# converter_schematic.net
KiCad netlist of a schematic drawn in EasyEDA
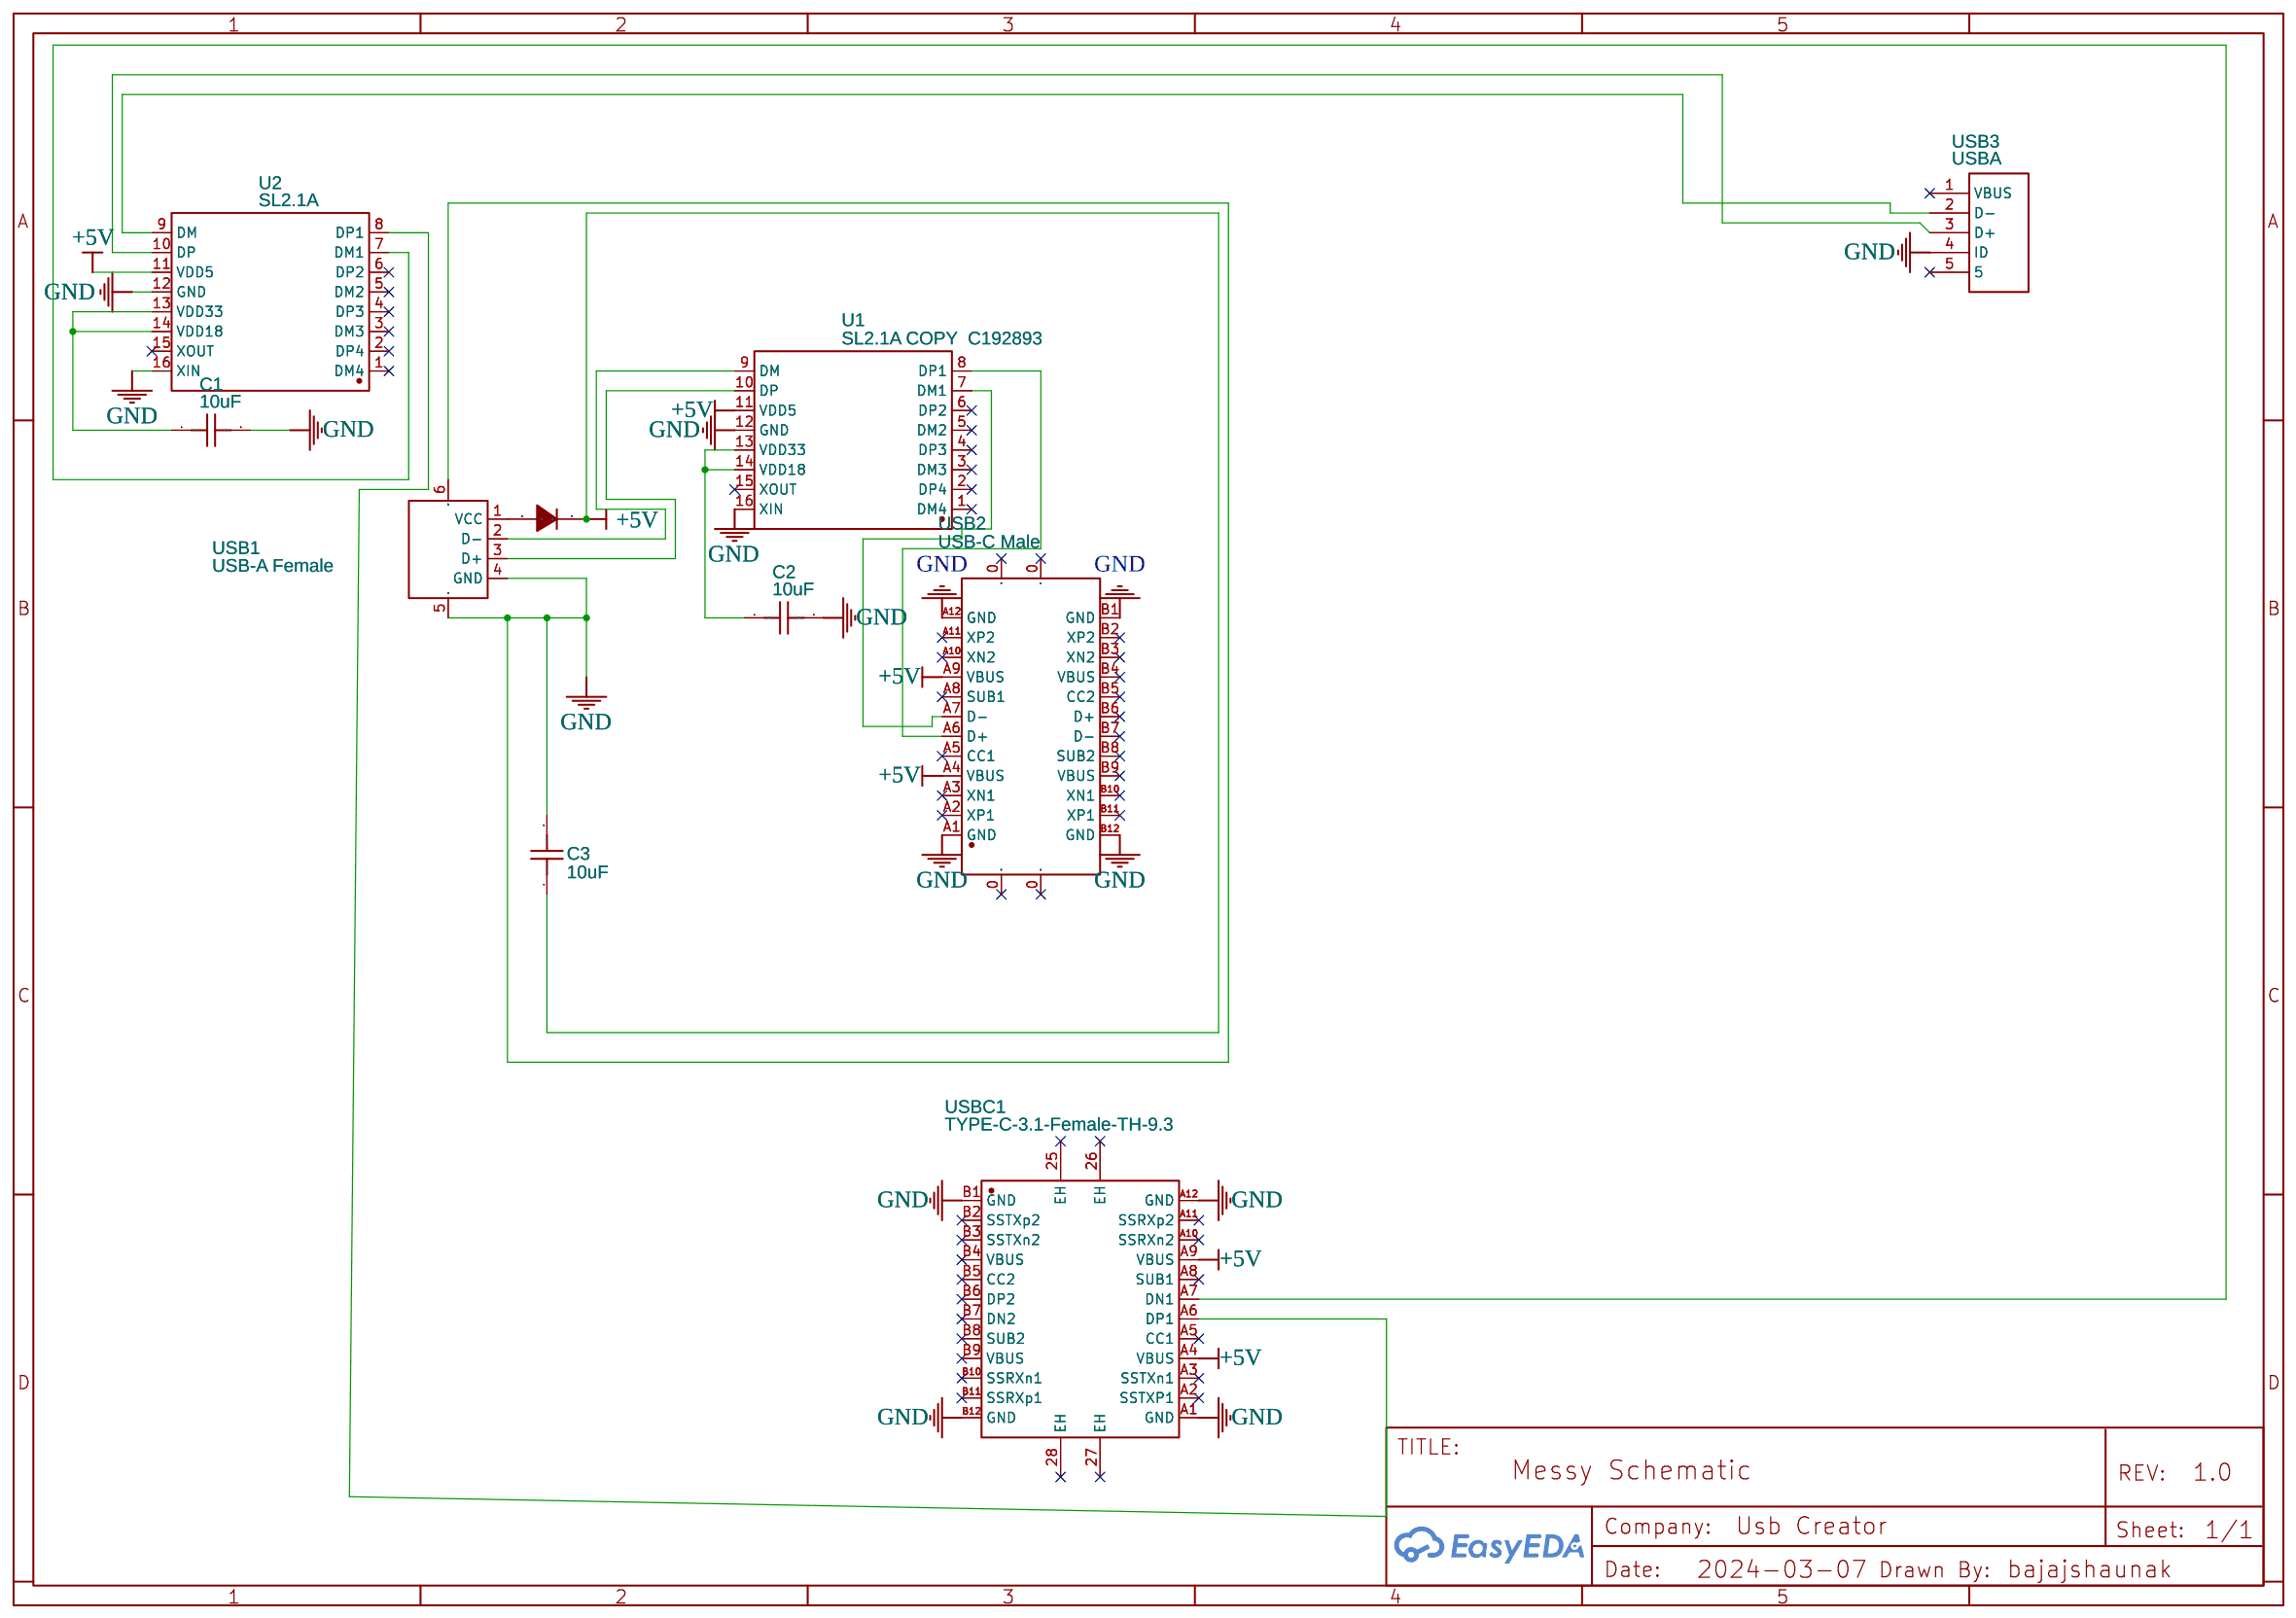
[diagram p0: schematic sheet]

(export (version "E")
  (design (tool "Eeschema 10.0.6"))
  (components
    (comp (ref "C1")
      (value "10uF")
      (fields
        (field (name "Manufacturer Part") "CL10A106KP8NNNC")
        (field (name "Manufacturer") "SAMSUNG(三星)")
      )
      (libsource (lib "") (part "CL10A106KP8NNNC"))
    )
    (comp (ref "C2")
      (value "10uF")
      (fields
        (field (name "Manufacturer Part") "CL10A106KP8NNNC")
        (field (name "Manufacturer") "SAMSUNG(三星)")
      )
      (libsource (lib "") (part "CL10A106KP8NNNC"))
    )
    (comp (ref "C3")
      (value "10uF")
      (fields
        (field (name "Manufacturer Part") "CL10A106KP8NNNC")
        (field (name "Manufacturer") "SAMSUNG(三星)")
      )
      (libsource (lib "") (part "CL10A106KP8NNNC_1"))
    )
    (comp (ref "D2")
      (value "NSR0320MW2T1G")
      (fields (field (name "Manufacturer") "onsemi(安森美)"))
      (libsource (lib "") (part "NSR0320MW2T1G"))
    )
    (comp (ref "U1")
      (value "SL2.1A COPY  C192893")
      (fields (field (name "Manufacturer Part") "SL2.1A") (field (name "Manufacturer") "CoreChips(和芯润德)"))
      (libsource (lib "") (part "SL2.1A COPY  C192893"))
    )
    (comp (ref "U2")
      (value "SL2.1A")
      (fields (field (name "Manufacturer") "CoreChips(和芯润德)"))
      (libsource (lib "") (part "SL2.1A"))
    )
    (comp (ref "USB1")
      (value "USB-A Female")
      (fields (field (name "Manufacturer Part") "USB-AF-DIP-154-HW-S") (field (name "Manufacturer") "皇捷"))
      (libsource (lib "") (part "USB-AF-DIP-154-HW-S"))
    )
    (comp (ref "USB2")
      (value "USB-C Male")
      (fields (field (name "Manufacturer Part") "USB-307HI") (field (name "Manufacturer") "HOOYA(皓宇电子)"))
      (libsource (lib "") (part "USB-307HI"))
    )
    (comp (ref "USB3")
      (value "USBA")
      (fields (field (name "Manufacturer Part") "U-USBAR04P-M001") (field (name "Manufacturer") "Ckmtw(灿科盟)"))
      (libsource (lib "") (part "U-USBAR04P-M002"))
    )
    (comp (ref "USBC1")
      (value "TYPE-C-3.1-Female-TH-9.3")
      (fields (field (name "Manufacturer Part") "918-418K2022Y40004") (field (name "Manufacturer") "精拓金"))
      (libsource (lib "") (part "TYPE-C-3.1-Female-TH-9.3"))
    )
  )
  (nets
    (net (code "1") (name "+5V") (class "Default")
      (node (ref "C3") (pin "1") (pinfunction "1_1") (pintype "unspecified"))
      (node (ref "D2") (pin "1") (pinfunction "C_1") (pintype "unspecified"))
      (node (ref "U1") (pin "11") (pinfunction "VDD5_11") (pintype "unspecified"))
      (node (ref "U2") (pin "11") (pinfunction "VDD5_11") (pintype "unspecified"))
      (node (ref "USB2") (pin "A4") (pinfunction "VBUS_A4") (pintype "unspecified"))
      (node (ref "USB2") (pin "A9") (pinfunction "VBUS_A9") (pintype "unspecified"))
      (node (ref "USBC1") (pin "A4") (pinfunction "VBUS_A4") (pintype "unspecified"))
      (node (ref "USBC1") (pin "A9") (pinfunction "VBUS_A9") (pintype "unspecified"))
    )
    (net (code "2") (name "GND") (class "Default")
      (node (ref "C1") (pin "2") (pinfunction "2_2") (pintype "unspecified"))
      (node (ref "C2") (pin "2") (pinfunction "2_2") (pintype "unspecified"))
      (node (ref "C3") (pin "2") (pinfunction "2_2") (pintype "unspecified"))
      (node (ref "U1") (pin "12") (pinfunction "GND_12") (pintype "unspecified"))
      (node (ref "U1") (pin "16") (pinfunction "XIN_16") (pintype "unspecified"))
      (node (ref "U2") (pin "12") (pinfunction "GND_12") (pintype "unspecified"))
      (node (ref "U2") (pin "16") (pinfunction "XIN_16") (pintype "unspecified"))
      (node (ref "USB1") (pin "4") (pinfunction "GND_4") (pintype "input"))
      (node (ref "USB1") (pin "5") (pinfunction "SH1_5") (pintype "unspecified"))
      (node (ref "USB1") (pin "6") (pinfunction "SH2_6") (pintype "unspecified"))
      (node (ref "USB2") (pin "A1") (pinfunction "GND_A1") (pintype "unspecified"))
      (node (ref "USB2") (pin "A12") (pinfunction "GND_A12") (pintype "unspecified"))
      (node (ref "USB2") (pin "B1") (pinfunction "GND_B1") (pintype "unspecified"))
      (node (ref "USB2") (pin "B12") (pinfunction "GND_B12") (pintype "unspecified"))
      (node (ref "USB3") (pin "4") (pinfunction "ID_4") (pintype "unspecified"))
      (node (ref "USBC1") (pin "A1") (pinfunction "GND_A1") (pintype "unspecified"))
      (node (ref "USBC1") (pin "A12") (pinfunction "GND_A12") (pintype "unspecified"))
      (node (ref "USBC1") (pin "B1") (pinfunction "GND_B1") (pintype "unspecified"))
      (node (ref "USBC1") (pin "B12") (pinfunction "GND_B12") (pintype "unspecified"))
    )
    (net (code "3") (name "Net-(D2-A)") (class "Default")
      (node (ref "D2") (pin "2") (pinfunction "A_2") (pintype "unspecified"))
      (node (ref "USB1") (pin "1") (pinfunction "VCC_1") (pintype "input"))
    )
    (net (code "4") (name "Net-(U1-DM)") (class "Default")
      (node (ref "U1") (pin "9") (pinfunction "DM_9") (pintype "unspecified"))
      (node (ref "USB1") (pin "2") (pinfunction "D-_2") (pintype "input"))
    )
    (net (code "5") (name "Net-(U1-DM1)") (class "Default")
      (node (ref "U1") (pin "7") (pinfunction "DM1_7") (pintype "unspecified"))
      (node (ref "USB2") (pin "A7") (pinfunction "D-_A7") (pintype "unspecified"))
    )
    (net (code "6") (name "Net-(U1-DP)") (class "Default")
      (node (ref "U1") (pin "10") (pinfunction "DP_10") (pintype "unspecified"))
      (node (ref "USB1") (pin "3") (pinfunction "D+_3") (pintype "input"))
    )
    (net (code "7") (name "Net-(U1-DP1)") (class "Default")
      (node (ref "U1") (pin "8") (pinfunction "DP1_8") (pintype "unspecified"))
      (node (ref "USB2") (pin "A6") (pinfunction "D+_A6") (pintype "unspecified"))
    )
    (net (code "8") (name "Net-(U1-VDD18)") (class "Default")
      (node (ref "C2") (pin "1") (pinfunction "1_1") (pintype "unspecified"))
      (node (ref "U1") (pin "13") (pinfunction "VDD33_13") (pintype "unspecified"))
      (node (ref "U1") (pin "14") (pinfunction "VDD18_14") (pintype "unspecified"))
    )
    (net (code "9") (name "Net-(U2-DM)") (class "Default")
      (node (ref "U2") (pin "9") (pinfunction "DM_9") (pintype "unspecified"))
      (node (ref "USB3") (pin "2") (pinfunction "D-_2") (pintype "unspecified"))
    )
    (net (code "10") (name "Net-(U2-DM1)") (class "Default")
      (node (ref "U2") (pin "7") (pinfunction "DM1_7") (pintype "unspecified"))
      (node (ref "USBC1") (pin "A7") (pinfunction "DN1_A7") (pintype "unspecified"))
    )
    (net (code "11") (name "Net-(U2-DP)") (class "Default")
      (node (ref "U2") (pin "10") (pinfunction "DP_10") (pintype "unspecified"))
      (node (ref "USB3") (pin "3") (pinfunction "D+_3") (pintype "unspecified"))
    )
    (net (code "12") (name "Net-(U2-DP1)") (class "Default")
      (node (ref "U2") (pin "8") (pinfunction "DP1_8") (pintype "unspecified"))
      (node (ref "USBC1") (pin "A6") (pinfunction "DP1_A6") (pintype "unspecified"))
    )
    (net (code "13") (name "Net-(U2-VDD18)") (class "Default")
      (node (ref "C1") (pin "1") (pinfunction "1_1") (pintype "unspecified"))
      (node (ref "U2") (pin "13") (pinfunction "VDD33_13") (pintype "unspecified"))
      (node (ref "U2") (pin "14") (pinfunction "VDD18_14") (pintype "unspecified"))
    )
    (net (code "14") (name "unconnected-(U1-DM2-Pad5)") (class "Default")
      (node (ref "U1") (pin "5") (pinfunction "DM2_5") (pintype "unspecified+no_connect"))
    )
    (net (code "15") (name "unconnected-(U1-DM3-Pad3)") (class "Default")
      (node (ref "U1") (pin "3") (pinfunction "DM3_3") (pintype "unspecified+no_connect"))
    )
    (net (code "16") (name "unconnected-(U1-DM4-Pad1)") (class "Default")
      (node (ref "U1") (pin "1") (pinfunction "DM4_1") (pintype "unspecified+no_connect"))
    )
    (net (code "17") (name "unconnected-(U1-DP2-Pad6)") (class "Default")
      (node (ref "U1") (pin "6") (pinfunction "DP2_6") (pintype "unspecified+no_connect"))
    )
    (net (code "18") (name "unconnected-(U1-DP3-Pad4)") (class "Default")
      (node (ref "U1") (pin "4") (pinfunction "DP3_4") (pintype "unspecified+no_connect"))
    )
    (net (code "19") (name "unconnected-(U1-DP4-Pad2)") (class "Default")
      (node (ref "U1") (pin "2") (pinfunction "DP4_2") (pintype "unspecified+no_connect"))
    )
    (net (code "20") (name "unconnected-(U1-XOUT-Pad15)") (class "Default")
      (node (ref "U1") (pin "15") (pinfunction "XOUT_15") (pintype "unspecified+no_connect"))
    )
    (net (code "21") (name "unconnected-(U2-DM2-Pad5)") (class "Default")
      (node (ref "U2") (pin "5") (pinfunction "DM2_5") (pintype "unspecified+no_connect"))
    )
    (net (code "22") (name "unconnected-(U2-DM3-Pad3)") (class "Default")
      (node (ref "U2") (pin "3") (pinfunction "DM3_3") (pintype "unspecified+no_connect"))
    )
    (net (code "23") (name "unconnected-(U2-DM4-Pad1)") (class "Default")
      (node (ref "U2") (pin "1") (pinfunction "DM4_1") (pintype "unspecified+no_connect"))
    )
    (net (code "24") (name "unconnected-(U2-DP2-Pad6)") (class "Default")
      (node (ref "U2") (pin "6") (pinfunction "DP2_6") (pintype "unspecified+no_connect"))
    )
    (net (code "25") (name "unconnected-(U2-DP3-Pad4)") (class "Default")
      (node (ref "U2") (pin "4") (pinfunction "DP3_4") (pintype "unspecified+no_connect"))
    )
    (net (code "26") (name "unconnected-(U2-DP4-Pad2)") (class "Default")
      (node (ref "U2") (pin "2") (pinfunction "DP4_2") (pintype "unspecified+no_connect"))
    )
    (net (code "27") (name "unconnected-(U2-XOUT-Pad15)") (class "Default")
      (node (ref "U2") (pin "15") (pinfunction "XOUT_15") (pintype "unspecified+no_connect"))
    )
    (net (code "28") (name "unconnected-(USB2-CC1-PadA5)") (class "Default")
      (node (ref "USB2") (pin "A5") (pinfunction "CC1_A5") (pintype "unspecified+no_connect"))
    )
    (net (code "29") (name "unconnected-(USB2-CC2-PadB5)") (class "Default")
      (node (ref "USB2") (pin "B5") (pinfunction "CC2_B5") (pintype "unspecified+no_connect"))
    )
    (net (code "30") (name "unconnected-(USB2-D+-PadB6)") (class "Default")
      (node (ref "USB2") (pin "B6") (pinfunction "D+_B6") (pintype "unspecified+no_connect"))
    )
    (net (code "31") (name "unconnected-(USB2-D--PadB7)") (class "Default")
      (node (ref "USB2") (pin "B7") (pinfunction "D-_B7") (pintype "unspecified+no_connect"))
    )
    (net (code "32") (name "unconnected-(USB2-Pad0)") (class "Default")
      (node (ref "USB2") (pin "0") (pinfunction "0_0") (pintype "unspecified+no_connect"))
    )
    (net (code "33") (name "unconnected-(USB2-Pad0)_1") (class "Default")
      (node (ref "USB2") (pin "0") (pinfunction "0_0") (pintype "unspecified+no_connect"))
    )
    (net (code "34") (name "unconnected-(USB2-Pad0)_2") (class "Default")
      (node (ref "USB2") (pin "0") (pinfunction "0_0") (pintype "unspecified+no_connect"))
    )
    (net (code "35") (name "unconnected-(USB2-Pad0)_3") (class "Default")
      (node (ref "USB2") (pin "0") (pinfunction "0_0") (pintype "unspecified+no_connect"))
    )
    (net (code "36") (name "unconnected-(USB2-SUB1-PadA8)") (class "Default")
      (node (ref "USB2") (pin "A8") (pinfunction "SUB1_A8") (pintype "unspecified+no_connect"))
    )
    (net (code "37") (name "unconnected-(USB2-SUB2-PadB8)") (class "Default")
      (node (ref "USB2") (pin "B8") (pinfunction "SUB2_B8") (pintype "unspecified+no_connect"))
    )
    (net (code "38") (name "unconnected-(USB2-VBUS-PadB4)") (class "Default")
      (node (ref "USB2") (pin "B4") (pinfunction "VBUS_B4") (pintype "unspecified+no_connect"))
    )
    (net (code "39") (name "unconnected-(USB2-VBUS-PadB9)") (class "Default")
      (node (ref "USB2") (pin "B9") (pinfunction "VBUS_B9") (pintype "unspecified+no_connect"))
    )
    (net (code "40") (name "unconnected-(USB2-XN1-PadA3)") (class "Default")
      (node (ref "USB2") (pin "A3") (pinfunction "XN1_A3") (pintype "unspecified+no_connect"))
    )
    (net (code "41") (name "unconnected-(USB2-XN1-PadB10)") (class "Default")
      (node (ref "USB2") (pin "B10") (pinfunction "XN1_B10") (pintype "unspecified+no_connect"))
    )
    (net (code "42") (name "unconnected-(USB2-XN2-PadA10)") (class "Default")
      (node (ref "USB2") (pin "A10") (pinfunction "XN2_A10") (pintype "unspecified+no_connect"))
    )
    (net (code "43") (name "unconnected-(USB2-XN2-PadB3)") (class "Default")
      (node (ref "USB2") (pin "B3") (pinfunction "XN2_B3") (pintype "unspecified+no_connect"))
    )
    (net (code "44") (name "unconnected-(USB2-XP1-PadA2)") (class "Default")
      (node (ref "USB2") (pin "A2") (pinfunction "XP1_A2") (pintype "unspecified+no_connect"))
    )
    (net (code "45") (name "unconnected-(USB2-XP1-PadB11)") (class "Default")
      (node (ref "USB2") (pin "B11") (pinfunction "XP1_B11") (pintype "unspecified+no_connect"))
    )
    (net (code "46") (name "unconnected-(USB2-XP2-PadA11)") (class "Default")
      (node (ref "USB2") (pin "A11") (pinfunction "XP2_A11") (pintype "unspecified+no_connect"))
    )
    (net (code "47") (name "unconnected-(USB2-XP2-PadB2)") (class "Default")
      (node (ref "USB2") (pin "B2") (pinfunction "XP2_B2") (pintype "unspecified+no_connect"))
    )
    (net (code "48") (name "unconnected-(USB3-Pad5)") (class "Default")
      (node (ref "USB3") (pin "5") (pinfunction "5_5") (pintype "unspecified+no_connect"))
    )
    (net (code "49") (name "unconnected-(USB3-VBUS-Pad1)") (class "Default")
      (node (ref "USB3") (pin "1") (pinfunction "VBUS_1") (pintype "unspecified+no_connect"))
    )
    (net (code "50") (name "unconnected-(USBC1-CC1-PadA5)") (class "Default")
      (node (ref "USBC1") (pin "A5") (pinfunction "CC1_A5") (pintype "unspecified+no_connect"))
    )
    (net (code "51") (name "unconnected-(USBC1-CC2-PadB5)") (class "Default")
      (node (ref "USBC1") (pin "B5") (pinfunction "CC2_B5") (pintype "unspecified+no_connect"))
    )
    (net (code "52") (name "unconnected-(USBC1-DN2-PadB7)") (class "Default")
      (node (ref "USBC1") (pin "B7") (pinfunction "DN2_B7") (pintype "unspecified+no_connect"))
    )
    (net (code "53") (name "unconnected-(USBC1-DP2-PadB6)") (class "Default")
      (node (ref "USBC1") (pin "B6") (pinfunction "DP2_B6") (pintype "unspecified+no_connect"))
    )
    (net (code "54") (name "unconnected-(USBC1-EH-Pad25)") (class "Default")
      (node (ref "USBC1") (pin "25") (pinfunction "EH_25") (pintype "unspecified+no_connect"))
    )
    (net (code "55") (name "unconnected-(USBC1-EH-Pad26)") (class "Default")
      (node (ref "USBC1") (pin "26") (pinfunction "EH_26") (pintype "unspecified+no_connect"))
    )
    (net (code "56") (name "unconnected-(USBC1-EH-Pad27)") (class "Default")
      (node (ref "USBC1") (pin "27") (pinfunction "EH_27") (pintype "unspecified+no_connect"))
    )
    (net (code "57") (name "unconnected-(USBC1-EH-Pad28)") (class "Default")
      (node (ref "USBC1") (pin "28") (pinfunction "EH_28") (pintype "unspecified+no_connect"))
    )
    (net (code "58") (name "unconnected-(USBC1-SSRXn1-PadB10)") (class "Default")
      (node (ref "USBC1") (pin "B10") (pinfunction "SSRXn1_B10") (pintype "unspecified+no_connect"))
    )
    (net (code "59") (name "unconnected-(USBC1-SSRXn2-PadA10)") (class "Default")
      (node (ref "USBC1") (pin "A10") (pinfunction "SSRXn2_A10") (pintype "unspecified+no_connect"))
    )
    (net (code "60") (name "unconnected-(USBC1-SSRXp1-PadB11)") (class "Default")
      (node (ref "USBC1") (pin "B11") (pinfunction "SSRXp1_B11") (pintype "unspecified+no_connect"))
    )
    (net (code "61") (name "unconnected-(USBC1-SSRXp2-PadA11)") (class "Default")
      (node (ref "USBC1") (pin "A11") (pinfunction "SSRXp2_A11") (pintype "unspecified+no_connect"))
    )
    (net (code "62") (name "unconnected-(USBC1-SSTXP1-PadA2)") (class "Default")
      (node (ref "USBC1") (pin "A2") (pinfunction "SSTXP1_A2") (pintype "unspecified+no_connect"))
    )
    (net (code "63") (name "unconnected-(USBC1-SSTXn1-PadA3)") (class "Default")
      (node (ref "USBC1") (pin "A3") (pinfunction "SSTXn1_A3") (pintype "unspecified+no_connect"))
    )
    (net (code "64") (name "unconnected-(USBC1-SSTXn2-PadB3)") (class "Default")
      (node (ref "USBC1") (pin "B3") (pinfunction "SSTXn2_B3") (pintype "unspecified+no_connect"))
    )
    (net (code "65") (name "unconnected-(USBC1-SSTXp2-PadB2)") (class "Default")
      (node (ref "USBC1") (pin "B2") (pinfunction "SSTXp2_B2") (pintype "unspecified+no_connect"))
    )
    (net (code "66") (name "unconnected-(USBC1-SUB1-PadA8)") (class "Default")
      (node (ref "USBC1") (pin "A8") (pinfunction "SUB1_A8") (pintype "unspecified+no_connect"))
    )
    (net (code "67") (name "unconnected-(USBC1-SUB2-PadB8)") (class "Default")
      (node (ref "USBC1") (pin "B8") (pinfunction "SUB2_B8") (pintype "unspecified+no_connect"))
    )
    (net (code "68") (name "unconnected-(USBC1-VBUS-PadB4)") (class "Default")
      (node (ref "USBC1") (pin "B4") (pinfunction "VBUS_B4") (pintype "unspecified+no_connect"))
    )
    (net (code "69") (name "unconnected-(USBC1-VBUS-PadB9)") (class "Default")
      (node (ref "USBC1") (pin "B9") (pinfunction "VBUS_B9") (pintype "unspecified+no_connect"))
    )
  )
)
